# Sheet1.net
KiCad netlist of a schematic drawn in Altium Designer
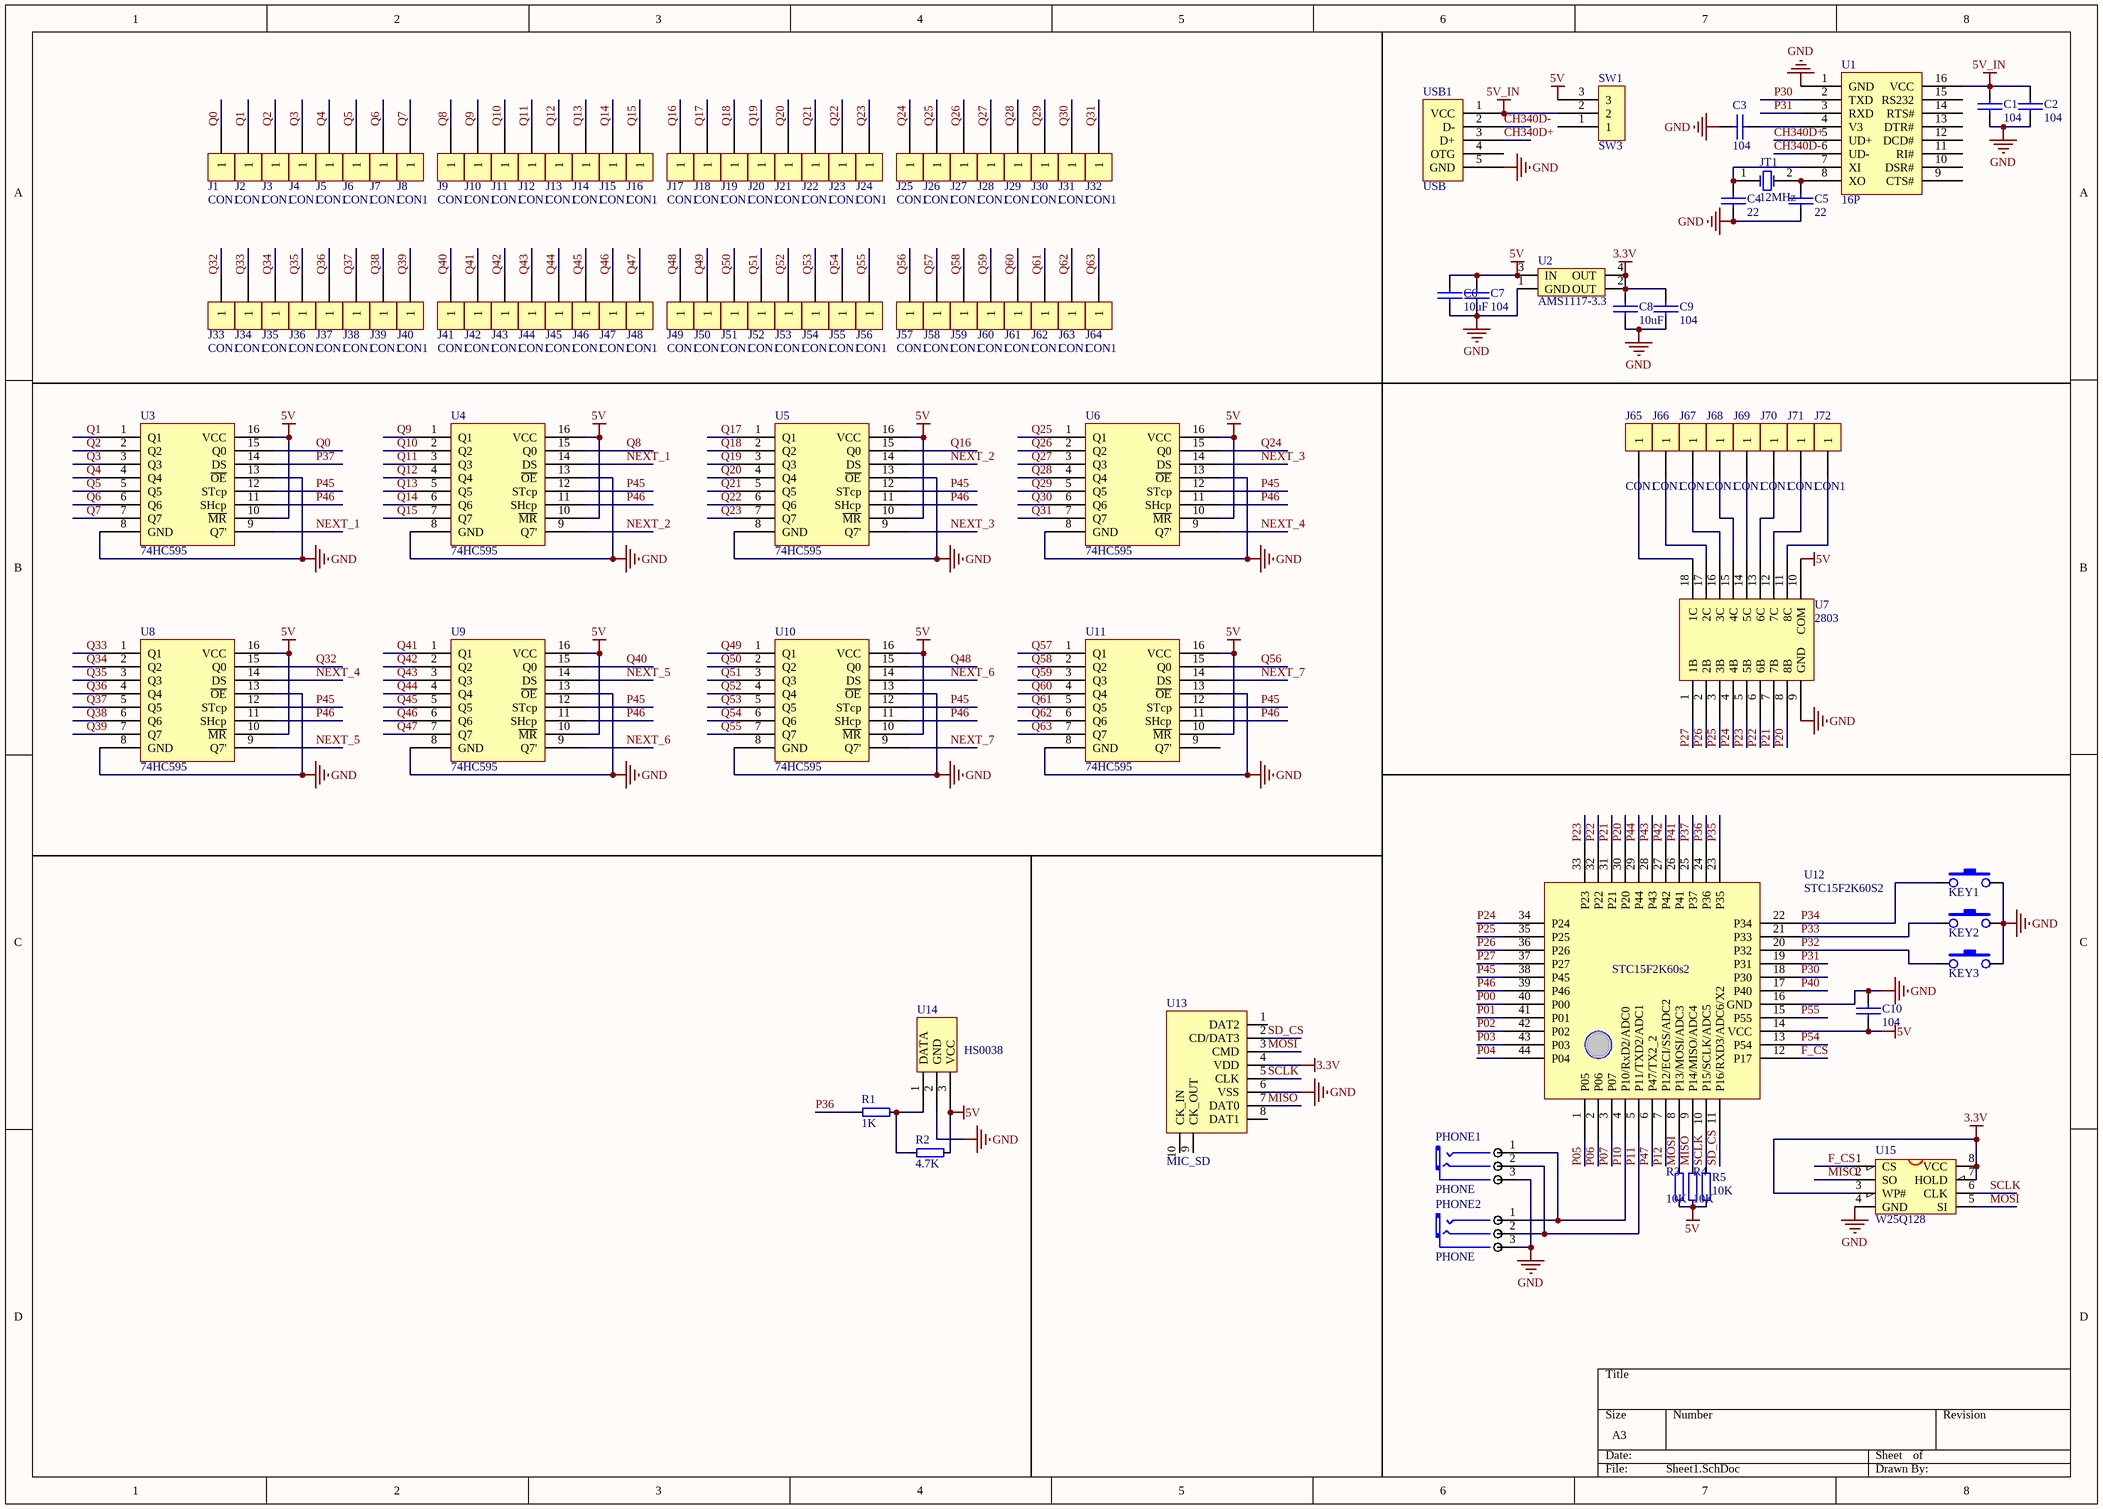
[diagram p0: Sheet1.SchDoc]

(export (version "E")
  (design (tool "Eeschema 10.0.6"))
  (components
    (comp (ref "C1") (value "104") (footprint "BY_魔法王子:0805C") (libsource (lib "BY_魔法王子") (part "CAP")))
    (comp (ref "C2") (value "104") (footprint "BY_魔法王子:0805C") (libsource (lib "BY_魔法王子") (part "CAP")))
    (comp (ref "C3") (value "104") (footprint "BY_魔法王子:0805C") (libsource (lib "BY_魔法王子") (part "CAP")))
    (comp (ref "C4") (value "22") (footprint "BY_魔法王子:0805C") (libsource (lib "BY_魔法王子") (part "CAP")))
    (comp (ref "C5") (value "22") (footprint "BY_魔法王子:0805C") (libsource (lib "BY_魔法王子") (part "CAP")))
    (comp (ref "C6") (value "10uF") (footprint "BY_魔法王子:0805C") (libsource (lib "BY_魔法王子") (part "CAP")))
    (comp (ref "C7") (value "104") (footprint "BY_魔法王子:0805C") (libsource (lib "BY_魔法王子") (part "CAP")))
    (comp (ref "C8") (value "10uF") (footprint "BY_魔法王子:0805C") (libsource (lib "BY_魔法王子") (part "CAP")))
    (comp (ref "C9") (value "104") (footprint "BY_魔法王子:0805C") (libsource (lib "BY_魔法王子") (part "CAP")))
    (comp (ref "C10") (value "104") (footprint "BY_魔法王子:0805C") (libsource (lib "BY_魔法王子") (part "CAP")))
    (comp (ref "J1")
      (value "CON1")
      (footprint "CON1")
      (description "Connector")
      (libsource (lib "插件") (part "CON1"))
    )
    (comp (ref "J2")
      (value "CON1")
      (footprint "CON1")
      (description "Connector")
      (libsource (lib "插件") (part "CON1"))
    )
    (comp (ref "J3")
      (value "CON1")
      (footprint "CON1")
      (description "Connector")
      (libsource (lib "插件") (part "CON1"))
    )
    (comp (ref "J4")
      (value "CON1")
      (footprint "CON1")
      (description "Connector")
      (libsource (lib "插件") (part "CON1"))
    )
    (comp (ref "J5")
      (value "CON1")
      (footprint "CON1")
      (description "Connector")
      (libsource (lib "插件") (part "CON1"))
    )
    (comp (ref "J6")
      (value "CON1")
      (footprint "CON1")
      (description "Connector")
      (libsource (lib "插件") (part "CON1"))
    )
    (comp (ref "J7")
      (value "CON1")
      (footprint "CON1")
      (description "Connector")
      (libsource (lib "插件") (part "CON1"))
    )
    (comp (ref "J8")
      (value "CON1")
      (footprint "CON1")
      (description "Connector")
      (libsource (lib "插件") (part "CON1"))
    )
    (comp (ref "J9")
      (value "CON1")
      (footprint "CON1")
      (description "Connector")
      (libsource (lib "插件") (part "CON1"))
    )
    (comp (ref "J10")
      (value "CON1")
      (footprint "CON1")
      (description "Connector")
      (libsource (lib "插件") (part "CON1"))
    )
    (comp (ref "J11")
      (value "CON1")
      (footprint "CON1")
      (description "Connector")
      (libsource (lib "插件") (part "CON1"))
    )
    (comp (ref "J12")
      (value "CON1")
      (footprint "CON1")
      (description "Connector")
      (libsource (lib "插件") (part "CON1"))
    )
    (comp (ref "J13")
      (value "CON1")
      (footprint "CON1")
      (description "Connector")
      (libsource (lib "插件") (part "CON1"))
    )
    (comp (ref "J14")
      (value "CON1")
      (footprint "CON1")
      (description "Connector")
      (libsource (lib "插件") (part "CON1"))
    )
    (comp (ref "J15")
      (value "CON1")
      (footprint "CON1")
      (description "Connector")
      (libsource (lib "插件") (part "CON1"))
    )
    (comp (ref "J16")
      (value "CON1")
      (footprint "CON1")
      (description "Connector")
      (libsource (lib "插件") (part "CON1"))
    )
    (comp (ref "J17")
      (value "CON1")
      (footprint "CON1")
      (description "Connector")
      (libsource (lib "插件") (part "CON1"))
    )
    (comp (ref "J18")
      (value "CON1")
      (footprint "CON1")
      (description "Connector")
      (libsource (lib "插件") (part "CON1"))
    )
    (comp (ref "J19")
      (value "CON1")
      (footprint "CON1")
      (description "Connector")
      (libsource (lib "插件") (part "CON1"))
    )
    (comp (ref "J20")
      (value "CON1")
      (footprint "CON1")
      (description "Connector")
      (libsource (lib "插件") (part "CON1"))
    )
    (comp (ref "J21")
      (value "CON1")
      (footprint "CON1")
      (description "Connector")
      (libsource (lib "插件") (part "CON1"))
    )
    (comp (ref "J22")
      (value "CON1")
      (footprint "CON1")
      (description "Connector")
      (libsource (lib "插件") (part "CON1"))
    )
    (comp (ref "J23")
      (value "CON1")
      (footprint "CON1")
      (description "Connector")
      (libsource (lib "插件") (part "CON1"))
    )
    (comp (ref "J24")
      (value "CON1")
      (footprint "CON1")
      (description "Connector")
      (libsource (lib "插件") (part "CON1"))
    )
    (comp (ref "J25")
      (value "CON1")
      (footprint "CON1")
      (description "Connector")
      (libsource (lib "插件") (part "CON1"))
    )
    (comp (ref "J26")
      (value "CON1")
      (footprint "CON1")
      (description "Connector")
      (libsource (lib "插件") (part "CON1"))
    )
    (comp (ref "J27")
      (value "CON1")
      (footprint "CON1")
      (description "Connector")
      (libsource (lib "插件") (part "CON1"))
    )
    (comp (ref "J28")
      (value "CON1")
      (footprint "CON1")
      (description "Connector")
      (libsource (lib "插件") (part "CON1"))
    )
    (comp (ref "J29")
      (value "CON1")
      (footprint "CON1")
      (description "Connector")
      (libsource (lib "插件") (part "CON1"))
    )
    (comp (ref "J30")
      (value "CON1")
      (footprint "CON1")
      (description "Connector")
      (libsource (lib "插件") (part "CON1"))
    )
    (comp (ref "J31")
      (value "CON1")
      (footprint "CON1")
      (description "Connector")
      (libsource (lib "插件") (part "CON1"))
    )
    (comp (ref "J32")
      (value "CON1")
      (footprint "CON1")
      (description "Connector")
      (libsource (lib "插件") (part "CON1"))
    )
    (comp (ref "J33")
      (value "CON1")
      (footprint "CON1")
      (description "Connector")
      (libsource (lib "插件") (part "CON1"))
    )
    (comp (ref "J34")
      (value "CON1")
      (footprint "CON1")
      (description "Connector")
      (libsource (lib "插件") (part "CON1"))
    )
    (comp (ref "J35")
      (value "CON1")
      (footprint "CON1")
      (description "Connector")
      (libsource (lib "插件") (part "CON1"))
    )
    (comp (ref "J36")
      (value "CON1")
      (footprint "CON1")
      (description "Connector")
      (libsource (lib "插件") (part "CON1"))
    )
    (comp (ref "J37")
      (value "CON1")
      (footprint "CON1")
      (description "Connector")
      (libsource (lib "插件") (part "CON1"))
    )
    (comp (ref "J38")
      (value "CON1")
      (footprint "CON1")
      (description "Connector")
      (libsource (lib "插件") (part "CON1"))
    )
    (comp (ref "J39")
      (value "CON1")
      (footprint "CON1")
      (description "Connector")
      (libsource (lib "插件") (part "CON1"))
    )
    (comp (ref "J40")
      (value "CON1")
      (footprint "CON1")
      (description "Connector")
      (libsource (lib "插件") (part "CON1"))
    )
    (comp (ref "J41")
      (value "CON1")
      (footprint "CON1")
      (description "Connector")
      (libsource (lib "插件") (part "CON1"))
    )
    (comp (ref "J42")
      (value "CON1")
      (footprint "CON1")
      (description "Connector")
      (libsource (lib "插件") (part "CON1"))
    )
    (comp (ref "J43")
      (value "CON1")
      (footprint "CON1")
      (description "Connector")
      (libsource (lib "插件") (part "CON1"))
    )
    (comp (ref "J44")
      (value "CON1")
      (footprint "CON1")
      (description "Connector")
      (libsource (lib "插件") (part "CON1"))
    )
    (comp (ref "J45")
      (value "CON1")
      (footprint "CON1")
      (description "Connector")
      (libsource (lib "插件") (part "CON1"))
    )
    (comp (ref "J46")
      (value "CON1")
      (footprint "CON1")
      (description "Connector")
      (libsource (lib "插件") (part "CON1"))
    )
    (comp (ref "J47")
      (value "CON1")
      (footprint "CON1")
      (description "Connector")
      (libsource (lib "插件") (part "CON1"))
    )
    (comp (ref "J48")
      (value "CON1")
      (footprint "CON1")
      (description "Connector")
      (libsource (lib "插件") (part "CON1"))
    )
    (comp (ref "J49")
      (value "CON1")
      (footprint "CON1")
      (description "Connector")
      (libsource (lib "插件") (part "CON1"))
    )
    (comp (ref "J50")
      (value "CON1")
      (footprint "CON1")
      (description "Connector")
      (libsource (lib "插件") (part "CON1"))
    )
    (comp (ref "J51")
      (value "CON1")
      (footprint "CON1")
      (description "Connector")
      (libsource (lib "插件") (part "CON1"))
    )
    (comp (ref "J52")
      (value "CON1")
      (footprint "CON1")
      (description "Connector")
      (libsource (lib "插件") (part "CON1"))
    )
    (comp (ref "J53")
      (value "CON1")
      (footprint "CON1")
      (description "Connector")
      (libsource (lib "插件") (part "CON1"))
    )
    (comp (ref "J54")
      (value "CON1")
      (footprint "CON1")
      (description "Connector")
      (libsource (lib "插件") (part "CON1"))
    )
    (comp (ref "J55")
      (value "CON1")
      (footprint "CON1")
      (description "Connector")
      (libsource (lib "插件") (part "CON1"))
    )
    (comp (ref "J56")
      (value "CON1")
      (footprint "CON1")
      (description "Connector")
      (libsource (lib "插件") (part "CON1"))
    )
    (comp (ref "J57")
      (value "CON1")
      (footprint "CON1")
      (description "Connector")
      (libsource (lib "插件") (part "CON1"))
    )
    (comp (ref "J58")
      (value "CON1")
      (footprint "CON1")
      (description "Connector")
      (libsource (lib "插件") (part "CON1"))
    )
    (comp (ref "J59")
      (value "CON1")
      (footprint "CON1")
      (description "Connector")
      (libsource (lib "插件") (part "CON1"))
    )
    (comp (ref "J60")
      (value "CON1")
      (footprint "CON1")
      (description "Connector")
      (libsource (lib "插件") (part "CON1"))
    )
    (comp (ref "J61")
      (value "CON1")
      (footprint "CON1")
      (description "Connector")
      (libsource (lib "插件") (part "CON1"))
    )
    (comp (ref "J62")
      (value "CON1")
      (footprint "CON1")
      (description "Connector")
      (libsource (lib "插件") (part "CON1"))
    )
    (comp (ref "J63")
      (value "CON1")
      (footprint "CON1")
      (description "Connector")
      (libsource (lib "插件") (part "CON1"))
    )
    (comp (ref "J64")
      (value "CON1")
      (footprint "CON1")
      (description "Connector")
      (libsource (lib "插件") (part "CON1"))
    )
    (comp (ref "J65")
      (value "CON1")
      (footprint "CON1")
      (description "Connector")
      (libsource (lib "") (part "CON1_1"))
    )
    (comp (ref "J66")
      (value "CON1")
      (footprint "CON1")
      (description "Connector")
      (libsource (lib "") (part "CON1_1"))
    )
    (comp (ref "J67")
      (value "CON1")
      (footprint "CON1")
      (description "Connector")
      (libsource (lib "") (part "CON1_1"))
    )
    (comp (ref "J68")
      (value "CON1")
      (footprint "CON1")
      (description "Connector")
      (libsource (lib "") (part "CON1_1"))
    )
    (comp (ref "J69")
      (value "CON1")
      (footprint "CON1")
      (description "Connector")
      (libsource (lib "") (part "CON1_1"))
    )
    (comp (ref "J70")
      (value "CON1")
      (footprint "CON1")
      (description "Connector")
      (libsource (lib "") (part "CON1_1"))
    )
    (comp (ref "J71")
      (value "CON1")
      (footprint "CON1")
      (description "Connector")
      (libsource (lib "") (part "CON1_1"))
    )
    (comp (ref "J72")
      (value "CON1")
      (footprint "CON1")
      (description "Connector")
      (libsource (lib "") (part "CON1_1"))
    )
    (comp (ref "JT1")
      (value "12MHz")
      (footprint "BY_魔法王子:JZ")
      (description "Crystal Oscillator")
      (fields (field (name "PUBLISHER") "Altium Limited"))
      (libsource (lib "Explorer STM32F407封装库") (part "XTAL"))
    )
    (comp (ref "KEY1") (value "KEY") (footprint "BY_魔法王子:KEY2") (libsource (lib "BY_魔法王子") (part "KEY")))
    (comp (ref "KEY2") (value "KEY") (footprint "BY_魔法王子:KEY2") (libsource (lib "BY_魔法王子") (part "KEY")))
    (comp (ref "KEY3") (value "KEY") (footprint "BY_魔法王子:KEY2") (libsource (lib "BY_魔法王子") (part "KEY")))
    (comp (ref "PHONE1")
      (value "PHONE")
      (footprint "PHONE_ST")
      (libsource (lib "Explorer STM32F407封装库") (part "PHONE_M"))
    )
    (comp (ref "PHONE2")
      (value "PHONE")
      (footprint "PHONE_ST")
      (libsource (lib "Explorer STM32F407封装库") (part "PHONE_M"))
    )
    (comp (ref "R1") (value "1K") (footprint "BY_魔法王子:0805R") (libsource (lib "BY_魔法王子") (part "RES")))
    (comp (ref "R2") (value "4.7K") (footprint "BY_魔法王子:0805R") (libsource (lib "BY_魔法王子") (part "RES")))
    (comp (ref "R3") (value "10K") (footprint "BY_魔法王子:0805R") (libsource (lib "BY_魔法王子") (part "RES")))
    (comp (ref "R4") (value "10K") (footprint "BY_魔法王子:0805R") (libsource (lib "BY_魔法王子") (part "RES")))
    (comp (ref "R5") (value "10K") (footprint "BY_魔法王子:0805R") (libsource (lib "BY_魔法王子") (part "RES")))
    (comp (ref "SW1") (value "SW3") (footprint "BY_魔法王子:SW3") (libsource (lib "BY_魔法王子") (part "SW3")))
    (comp (ref "U1") (value "16P") (footprint "CH340G") (libsource (lib "CH340G") (part "CH340G")))
    (comp (ref "U2")
      (value "AMS1117-3.3")
      (footprint "AMS1117")
      (libsource (lib "Explorer STM32F407封装库") (part "AMS1117"))
    )
    (comp (ref "U3") (value "74HC595") (footprint "SO-16N") (libsource (lib "74HC595") (part "74HC595")))
    (comp (ref "U4") (value "74HC595") (footprint "SO-16N") (libsource (lib "74HC595") (part "74HC595")))
    (comp (ref "U5") (value "74HC595") (footprint "SO-16N") (libsource (lib "74HC595") (part "74HC595")))
    (comp (ref "U6") (value "74HC595") (footprint "SO-16N") (libsource (lib "74HC595") (part "74HC595")))
    (comp (ref "U7") (value "2803") (footprint "BY_魔法王子:SOP-18") (libsource (lib "MISCESCH") (part "2803")))
    (comp (ref "U8") (value "74HC595") (footprint "SO-16N") (libsource (lib "74HC595") (part "74HC595")))
    (comp (ref "U9") (value "74HC595") (footprint "SO-16N") (libsource (lib "74HC595") (part "74HC595")))
    (comp (ref "U10") (value "74HC595") (footprint "SO-16N") (libsource (lib "74HC595") (part "74HC595")))
    (comp (ref "U11") (value "74HC595") (footprint "SO-16N") (libsource (lib "74HC595") (part "74HC595")))
    (comp (ref "U12")
      (value "STC15F2K60S2")
      (footprint "BY_魔法王子:STC15F2K60S2")
      (libsource (lib "BY_魔法王子") (part "STC15F2K60S2"))
    )
    (comp (ref "U13")
      (value "MIC_SD")
      (footprint "BY_魔法王子:TF_CARD")
      (libsource (lib "BY_魔法王子") (part "MICSD"))
    )
    (comp (ref "U14")
      (value "HS0038")
      (footprint "HS0038")
      (libsource (lib "Explorer STM32F407封装库") (part "HS0038"))
    )
    (comp (ref "U15")
      (value "W25Q128")
      (footprint "SOIC-8")
      (description "W25X16;SST25VF016;MX25L1605")
      (libsource (lib "Explorer STM32F407封装库") (part "W25X16"))
    )
    (comp (ref "USB1") (value "USB") (footprint "MINIUSB") (libsource (lib "MIN_USB") (part "MINIUSB")))
  )
  (nets
    (net (code "1") (name "/CH340D+") (class "Default")
      (node (ref "U1") (pin "5") (pinfunction "UD+_5") (pintype "passive"))
      (node (ref "USB1") (pin "3") (pinfunction "D+_3") (pintype "passive"))
    )
    (net (code "2") (name "/CH340D-") (class "Default")
      (node (ref "U1") (pin "6") (pinfunction "UD-_6") (pintype "passive"))
      (node (ref "USB1") (pin "2") (pinfunction "D-_2") (pintype "passive"))
    )
    (net (code "3") (name "/F_CS") (class "Default")
      (node (ref "U12") (pin "12") (pinfunction "P17_12") (pintype "passive"))
      (node (ref "U15") (pin "1") (pinfunction "CS_1") (pintype "passive"))
    )
    (net (code "4") (name "/MISO") (class "Default")
      (node (ref "R4") (pin "2") (pinfunction "2_2") (pintype "passive"))
      (node (ref "U12") (pin "9") (pinfunction "P14/MISO/ADC4_9") (pintype "passive"))
      (node (ref "U13") (pin "7") (pinfunction "DAT0_7") (pintype "passive"))
      (node (ref "U15") (pin "2") (pinfunction "SO_2") (pintype "passive"))
    )
    (net (code "5") (name "/MOSI") (class "Default")
      (node (ref "R3") (pin "2") (pinfunction "2_2") (pintype "passive"))
      (node (ref "U12") (pin "8") (pinfunction "P13/MOSI/ADC3_8") (pintype "passive"))
      (node (ref "U13") (pin "3") (pinfunction "CMD_3") (pintype "passive"))
      (node (ref "U15") (pin "5") (pinfunction "SI_5") (pintype "passive"))
    )
    (net (code "6") (name "/NEXT_1") (class "Default")
      (node (ref "U3") (pin "9") (pinfunction "Q7'_9") (pintype "passive"))
      (node (ref "U4") (pin "14") (pinfunction "DS_14") (pintype "passive"))
    )
    (net (code "7") (name "/NEXT_2") (class "Default")
      (node (ref "U4") (pin "9") (pinfunction "Q7'_9") (pintype "passive"))
      (node (ref "U5") (pin "14") (pinfunction "DS_14") (pintype "passive"))
    )
    (net (code "8") (name "/NEXT_3") (class "Default")
      (node (ref "U5") (pin "9") (pinfunction "Q7'_9") (pintype "passive"))
      (node (ref "U6") (pin "14") (pinfunction "DS_14") (pintype "passive"))
    )
    (net (code "9") (name "/NEXT_4") (class "Default")
      (node (ref "U6") (pin "9") (pinfunction "Q7'_9") (pintype "passive"))
      (node (ref "U8") (pin "14") (pinfunction "DS_14") (pintype "passive"))
    )
    (net (code "10") (name "/NEXT_5") (class "Default")
      (node (ref "U8") (pin "9") (pinfunction "Q7'_9") (pintype "passive"))
      (node (ref "U9") (pin "14") (pinfunction "DS_14") (pintype "passive"))
    )
    (net (code "11") (name "/NEXT_6") (class "Default")
      (node (ref "U10") (pin "14") (pinfunction "DS_14") (pintype "passive"))
      (node (ref "U9") (pin "9") (pinfunction "Q7'_9") (pintype "passive"))
    )
    (net (code "12") (name "/NEXT_7") (class "Default")
      (node (ref "U10") (pin "9") (pinfunction "Q7'_9") (pintype "passive"))
      (node (ref "U11") (pin "14") (pinfunction "DS_14") (pintype "passive"))
    )
    (net (code "13") (name "/P00") (class "Default")
      (node (ref "U12") (pin "40") (pinfunction "P00_40") (pintype "passive"))
    )
    (net (code "14") (name "/P01") (class "Default")
      (node (ref "U12") (pin "41") (pinfunction "P01_41") (pintype "passive"))
    )
    (net (code "15") (name "/P02") (class "Default")
      (node (ref "U12") (pin "42") (pinfunction "P02_42") (pintype "passive"))
    )
    (net (code "16") (name "/P03") (class "Default")
      (node (ref "U12") (pin "43") (pinfunction "P03_43") (pintype "passive"))
    )
    (net (code "17") (name "/P04") (class "Default")
      (node (ref "U12") (pin "44") (pinfunction "P04_44") (pintype "passive"))
    )
    (net (code "18") (name "/P05") (class "Default")
      (node (ref "U12") (pin "1") (pinfunction "P05_1") (pintype "passive"))
    )
    (net (code "19") (name "/P06") (class "Default")
      (node (ref "U12") (pin "2") (pinfunction "P06_2") (pintype "passive"))
    )
    (net (code "20") (name "/P07") (class "Default")
      (node (ref "U12") (pin "3") (pinfunction "P07_3") (pintype "passive"))
    )
    (net (code "21") (name "/P10") (class "Default")
      (node (ref "PHONE1") (pin "1") (pinfunction "CHL_1") (pintype "passive"))
      (node (ref "PHONE2") (pin "1") (pinfunction "CHL_1") (pintype "passive"))
      (node (ref "U12") (pin "4") (pinfunction "P10/RxD2/ADC0_4") (pintype "passive"))
    )
    (net (code "22") (name "/P11") (class "Default")
      (node (ref "PHONE1") (pin "2") (pinfunction "CHR_2") (pintype "passive"))
      (node (ref "PHONE2") (pin "2") (pinfunction "CHR_2") (pintype "passive"))
      (node (ref "U12") (pin "5") (pinfunction "P11/TXD2/ADC1_5") (pintype "passive"))
    )
    (net (code "23") (name "/P12") (class "Default")
      (node (ref "U12") (pin "7") (pinfunction "P12/ECI/SS/ADC2_7") (pintype "passive"))
    )
    (net (code "24") (name "/P20") (class "Default")
      (node (ref "U12") (pin "30") (pinfunction "P20_30") (pintype "passive"))
      (node (ref "U7") (pin "8") (pinfunction "8B_8") (pintype "passive"))
    )
    (net (code "25") (name "/P21") (class "Default")
      (node (ref "U12") (pin "31") (pinfunction "P21_31") (pintype "passive"))
      (node (ref "U7") (pin "7") (pinfunction "7B_7") (pintype "passive"))
    )
    (net (code "26") (name "/P22") (class "Default")
      (node (ref "U12") (pin "32") (pinfunction "P22_32") (pintype "passive"))
      (node (ref "U7") (pin "6") (pinfunction "6B_6") (pintype "passive"))
    )
    (net (code "27") (name "/P23") (class "Default")
      (node (ref "U12") (pin "33") (pinfunction "P23_33") (pintype "passive"))
      (node (ref "U7") (pin "5") (pinfunction "5B_5") (pintype "passive"))
    )
    (net (code "28") (name "/P24") (class "Default")
      (node (ref "U12") (pin "34") (pinfunction "P24_34") (pintype "passive"))
      (node (ref "U7") (pin "4") (pinfunction "4B_4") (pintype "passive"))
    )
    (net (code "29") (name "/P25") (class "Default")
      (node (ref "U12") (pin "35") (pinfunction "P25_35") (pintype "passive"))
      (node (ref "U7") (pin "3") (pinfunction "3B_3") (pintype "passive"))
    )
    (net (code "30") (name "/P26") (class "Default")
      (node (ref "U12") (pin "36") (pinfunction "P26_36") (pintype "passive"))
      (node (ref "U7") (pin "2") (pinfunction "2B_2") (pintype "passive"))
    )
    (net (code "31") (name "/P27") (class "Default")
      (node (ref "U12") (pin "37") (pinfunction "P27_37") (pintype "passive"))
      (node (ref "U7") (pin "1") (pinfunction "1B_1") (pintype "passive"))
    )
    (net (code "32") (name "/P30") (class "Default")
      (node (ref "U1") (pin "2") (pinfunction "TXD_2") (pintype "passive"))
      (node (ref "U12") (pin "18") (pinfunction "P30_18") (pintype "passive"))
    )
    (net (code "33") (name "/P31") (class "Default")
      (node (ref "U1") (pin "3") (pinfunction "RXD_3") (pintype "passive"))
      (node (ref "U12") (pin "19") (pinfunction "P31_19") (pintype "passive"))
    )
    (net (code "34") (name "/P32") (class "Default")
      (node (ref "KEY3") (pin "1") (pinfunction "1_1") (pintype "passive"))
      (node (ref "U12") (pin "20") (pinfunction "P32_20") (pintype "passive"))
    )
    (net (code "35") (name "/P33") (class "Default")
      (node (ref "KEY2") (pin "1") (pinfunction "1_1") (pintype "passive"))
      (node (ref "U12") (pin "21") (pinfunction "P33_21") (pintype "passive"))
    )
    (net (code "36") (name "/P34") (class "Default")
      (node (ref "KEY1") (pin "1") (pinfunction "1_1") (pintype "passive"))
      (node (ref "U12") (pin "22") (pinfunction "P34_22") (pintype "passive"))
    )
    (net (code "37") (name "/P35") (class "Default")
      (node (ref "U12") (pin "23") (pinfunction "P35_23") (pintype "passive"))
    )
    (net (code "38") (name "/P36") (class "Default")
      (node (ref "R1") (pin "2") (pinfunction "2_2") (pintype "passive"))
      (node (ref "U12") (pin "24") (pinfunction "P36_24") (pintype "passive"))
    )
    (net (code "39") (name "/P37") (class "Default")
      (node (ref "U12") (pin "25") (pinfunction "P37_25") (pintype "passive"))
      (node (ref "U3") (pin "14") (pinfunction "DS_14") (pintype "passive"))
    )
    (net (code "40") (name "/P40") (class "Default")
      (node (ref "U12") (pin "17") (pinfunction "P40_17") (pintype "passive"))
    )
    (net (code "41") (name "/P41") (class "Default")
      (node (ref "U12") (pin "26") (pinfunction "P41_26") (pintype "passive"))
    )
    (net (code "42") (name "/P42") (class "Default")
      (node (ref "U12") (pin "27") (pinfunction "P42_27") (pintype "passive"))
    )
    (net (code "43") (name "/P43") (class "Default")
      (node (ref "U12") (pin "28") (pinfunction "P43_28") (pintype "passive"))
    )
    (net (code "44") (name "/P44") (class "Default")
      (node (ref "U12") (pin "29") (pinfunction "P44_29") (pintype "passive"))
    )
    (net (code "45") (name "/P45") (class "Default")
      (node (ref "U10") (pin "12") (pinfunction "STcp_12") (pintype "passive"))
      (node (ref "U11") (pin "12") (pinfunction "STcp_12") (pintype "passive"))
      (node (ref "U12") (pin "38") (pinfunction "P45_38") (pintype "passive"))
      (node (ref "U3") (pin "12") (pinfunction "STcp_12") (pintype "passive"))
      (node (ref "U4") (pin "12") (pinfunction "STcp_12") (pintype "passive"))
      (node (ref "U5") (pin "12") (pinfunction "STcp_12") (pintype "passive"))
      (node (ref "U6") (pin "12") (pinfunction "STcp_12") (pintype "passive"))
      (node (ref "U8") (pin "12") (pinfunction "STcp_12") (pintype "passive"))
      (node (ref "U9") (pin "12") (pinfunction "STcp_12") (pintype "passive"))
    )
    (net (code "46") (name "/P46") (class "Default")
      (node (ref "U10") (pin "11") (pinfunction "SHcp_11") (pintype "passive"))
      (node (ref "U11") (pin "11") (pinfunction "SHcp_11") (pintype "passive"))
      (node (ref "U12") (pin "39") (pinfunction "P46_39") (pintype "passive"))
      (node (ref "U3") (pin "11") (pinfunction "SHcp_11") (pintype "passive"))
      (node (ref "U4") (pin "11") (pinfunction "SHcp_11") (pintype "passive"))
      (node (ref "U5") (pin "11") (pinfunction "SHcp_11") (pintype "passive"))
      (node (ref "U6") (pin "11") (pinfunction "SHcp_11") (pintype "passive"))
      (node (ref "U8") (pin "11") (pinfunction "SHcp_11") (pintype "passive"))
      (node (ref "U9") (pin "11") (pinfunction "SHcp_11") (pintype "passive"))
    )
    (net (code "47") (name "/P47") (class "Default")
      (node (ref "U12") (pin "6") (pinfunction "P47/TX2_2_6") (pintype "passive"))
    )
    (net (code "48") (name "/P54") (class "Default")
      (node (ref "U12") (pin "13") (pinfunction "P54_13") (pintype "passive"))
    )
    (net (code "49") (name "/P55") (class "Default")
      (node (ref "U12") (pin "15") (pinfunction "P55_15") (pintype "passive"))
    )
    (net (code "50") (name "/Q0") (class "Default")
      (node (ref "J1") (pin "1") (pinfunction "1_1") (pintype "passive"))
      (node (ref "U3") (pin "15") (pinfunction "Q0_15") (pintype "passive"))
    )
    (net (code "51") (name "/Q1") (class "Default")
      (node (ref "J2") (pin "1") (pinfunction "1_1") (pintype "passive"))
      (node (ref "U3") (pin "1") (pinfunction "Q1_1") (pintype "passive"))
    )
    (net (code "52") (name "/Q2") (class "Default")
      (node (ref "J3") (pin "1") (pinfunction "1_1") (pintype "passive"))
      (node (ref "U3") (pin "2") (pinfunction "Q2_2") (pintype "passive"))
    )
    (net (code "53") (name "/Q3") (class "Default")
      (node (ref "J4") (pin "1") (pinfunction "1_1") (pintype "passive"))
      (node (ref "U3") (pin "3") (pinfunction "Q3_3") (pintype "passive"))
    )
    (net (code "54") (name "/Q4") (class "Default")
      (node (ref "J5") (pin "1") (pinfunction "1_1") (pintype "passive"))
      (node (ref "U3") (pin "4") (pinfunction "Q4_4") (pintype "passive"))
    )
    (net (code "55") (name "/Q5") (class "Default")
      (node (ref "J6") (pin "1") (pinfunction "1_1") (pintype "passive"))
      (node (ref "U3") (pin "5") (pinfunction "Q5_5") (pintype "passive"))
    )
    (net (code "56") (name "/Q6") (class "Default")
      (node (ref "J7") (pin "1") (pinfunction "1_1") (pintype "passive"))
      (node (ref "U3") (pin "6") (pinfunction "Q6_6") (pintype "passive"))
    )
    (net (code "57") (name "/Q7") (class "Default")
      (node (ref "J8") (pin "1") (pinfunction "1_1") (pintype "passive"))
      (node (ref "U3") (pin "7") (pinfunction "Q7_7") (pintype "passive"))
    )
    (net (code "58") (name "/Q8") (class "Default")
      (node (ref "J9") (pin "1") (pinfunction "1_1") (pintype "passive"))
      (node (ref "U4") (pin "15") (pinfunction "Q0_15") (pintype "passive"))
    )
    (net (code "59") (name "/Q9") (class "Default")
      (node (ref "J10") (pin "1") (pinfunction "1_1") (pintype "passive"))
      (node (ref "U4") (pin "1") (pinfunction "Q1_1") (pintype "passive"))
    )
    (net (code "60") (name "/Q10") (class "Default")
      (node (ref "J11") (pin "1") (pinfunction "1_1") (pintype "passive"))
      (node (ref "U4") (pin "2") (pinfunction "Q2_2") (pintype "passive"))
    )
    (net (code "61") (name "/Q11") (class "Default")
      (node (ref "J12") (pin "1") (pinfunction "1_1") (pintype "passive"))
      (node (ref "U4") (pin "3") (pinfunction "Q3_3") (pintype "passive"))
    )
    (net (code "62") (name "/Q12") (class "Default")
      (node (ref "J13") (pin "1") (pinfunction "1_1") (pintype "passive"))
      (node (ref "U4") (pin "4") (pinfunction "Q4_4") (pintype "passive"))
    )
    (net (code "63") (name "/Q13") (class "Default")
      (node (ref "J14") (pin "1") (pinfunction "1_1") (pintype "passive"))
      (node (ref "U4") (pin "5") (pinfunction "Q5_5") (pintype "passive"))
    )
    (net (code "64") (name "/Q14") (class "Default")
      (node (ref "J15") (pin "1") (pinfunction "1_1") (pintype "passive"))
      (node (ref "U4") (pin "6") (pinfunction "Q6_6") (pintype "passive"))
    )
    (net (code "65") (name "/Q15") (class "Default")
      (node (ref "J16") (pin "1") (pinfunction "1_1") (pintype "passive"))
      (node (ref "U4") (pin "7") (pinfunction "Q7_7") (pintype "passive"))
    )
    (net (code "66") (name "/Q16") (class "Default")
      (node (ref "J17") (pin "1") (pinfunction "1_1") (pintype "passive"))
      (node (ref "U5") (pin "15") (pinfunction "Q0_15") (pintype "passive"))
    )
    (net (code "67") (name "/Q17") (class "Default")
      (node (ref "J18") (pin "1") (pinfunction "1_1") (pintype "passive"))
      (node (ref "U5") (pin "1") (pinfunction "Q1_1") (pintype "passive"))
    )
    (net (code "68") (name "/Q18") (class "Default")
      (node (ref "J19") (pin "1") (pinfunction "1_1") (pintype "passive"))
      (node (ref "U5") (pin "2") (pinfunction "Q2_2") (pintype "passive"))
    )
    (net (code "69") (name "/Q19") (class "Default")
      (node (ref "J20") (pin "1") (pinfunction "1_1") (pintype "passive"))
      (node (ref "U5") (pin "3") (pinfunction "Q3_3") (pintype "passive"))
    )
    (net (code "70") (name "/Q20") (class "Default")
      (node (ref "J21") (pin "1") (pinfunction "1_1") (pintype "passive"))
      (node (ref "U5") (pin "4") (pinfunction "Q4_4") (pintype "passive"))
    )
    (net (code "71") (name "/Q21") (class "Default")
      (node (ref "J22") (pin "1") (pinfunction "1_1") (pintype "passive"))
      (node (ref "U5") (pin "5") (pinfunction "Q5_5") (pintype "passive"))
    )
    (net (code "72") (name "/Q22") (class "Default")
      (node (ref "J23") (pin "1") (pinfunction "1_1") (pintype "passive"))
      (node (ref "U5") (pin "6") (pinfunction "Q6_6") (pintype "passive"))
    )
    (net (code "73") (name "/Q23") (class "Default")
      (node (ref "J24") (pin "1") (pinfunction "1_1") (pintype "passive"))
      (node (ref "U5") (pin "7") (pinfunction "Q7_7") (pintype "passive"))
    )
    (net (code "74") (name "/Q24") (class "Default")
      (node (ref "J25") (pin "1") (pinfunction "1_1") (pintype "passive"))
      (node (ref "U6") (pin "15") (pinfunction "Q0_15") (pintype "passive"))
    )
    (net (code "75") (name "/Q25") (class "Default")
      (node (ref "J26") (pin "1") (pinfunction "1_1") (pintype "passive"))
      (node (ref "U6") (pin "1") (pinfunction "Q1_1") (pintype "passive"))
    )
    (net (code "76") (name "/Q26") (class "Default")
      (node (ref "J27") (pin "1") (pinfunction "1_1") (pintype "passive"))
      (node (ref "U6") (pin "2") (pinfunction "Q2_2") (pintype "passive"))
    )
    (net (code "77") (name "/Q27") (class "Default")
      (node (ref "J28") (pin "1") (pinfunction "1_1") (pintype "passive"))
      (node (ref "U6") (pin "3") (pinfunction "Q3_3") (pintype "passive"))
    )
    (net (code "78") (name "/Q28") (class "Default")
      (node (ref "J29") (pin "1") (pinfunction "1_1") (pintype "passive"))
      (node (ref "U6") (pin "4") (pinfunction "Q4_4") (pintype "passive"))
    )
    (net (code "79") (name "/Q29") (class "Default")
      (node (ref "J30") (pin "1") (pinfunction "1_1") (pintype "passive"))
      (node (ref "U6") (pin "5") (pinfunction "Q5_5") (pintype "passive"))
    )
    (net (code "80") (name "/Q30") (class "Default")
      (node (ref "J31") (pin "1") (pinfunction "1_1") (pintype "passive"))
      (node (ref "U6") (pin "6") (pinfunction "Q6_6") (pintype "passive"))
    )
    (net (code "81") (name "/Q31") (class "Default")
      (node (ref "J32") (pin "1") (pinfunction "1_1") (pintype "passive"))
      (node (ref "U6") (pin "7") (pinfunction "Q7_7") (pintype "passive"))
    )
    (net (code "82") (name "/Q32") (class "Default")
      (node (ref "J33") (pin "1") (pinfunction "1_1") (pintype "passive"))
      (node (ref "U8") (pin "15") (pinfunction "Q0_15") (pintype "passive"))
    )
    (net (code "83") (name "/Q33") (class "Default")
      (node (ref "J34") (pin "1") (pinfunction "1_1") (pintype "passive"))
      (node (ref "U8") (pin "1") (pinfunction "Q1_1") (pintype "passive"))
    )
    (net (code "84") (name "/Q34") (class "Default")
      (node (ref "J35") (pin "1") (pinfunction "1_1") (pintype "passive"))
      (node (ref "U8") (pin "2") (pinfunction "Q2_2") (pintype "passive"))
    )
    (net (code "85") (name "/Q35") (class "Default")
      (node (ref "J36") (pin "1") (pinfunction "1_1") (pintype "passive"))
      (node (ref "U8") (pin "3") (pinfunction "Q3_3") (pintype "passive"))
    )
    (net (code "86") (name "/Q36") (class "Default")
      (node (ref "J37") (pin "1") (pinfunction "1_1") (pintype "passive"))
      (node (ref "U8") (pin "4") (pinfunction "Q4_4") (pintype "passive"))
    )
    (net (code "87") (name "/Q37") (class "Default")
      (node (ref "J38") (pin "1") (pinfunction "1_1") (pintype "passive"))
      (node (ref "U8") (pin "5") (pinfunction "Q5_5") (pintype "passive"))
    )
    (net (code "88") (name "/Q38") (class "Default")
      (node (ref "J39") (pin "1") (pinfunction "1_1") (pintype "passive"))
      (node (ref "U8") (pin "6") (pinfunction "Q6_6") (pintype "passive"))
    )
    (net (code "89") (name "/Q39") (class "Default")
      (node (ref "J40") (pin "1") (pinfunction "1_1") (pintype "passive"))
      (node (ref "U8") (pin "7") (pinfunction "Q7_7") (pintype "passive"))
    )
    (net (code "90") (name "/Q40") (class "Default")
      (node (ref "J41") (pin "1") (pinfunction "1_1") (pintype "passive"))
      (node (ref "U9") (pin "15") (pinfunction "Q0_15") (pintype "passive"))
    )
    (net (code "91") (name "/Q41") (class "Default")
      (node (ref "J42") (pin "1") (pinfunction "1_1") (pintype "passive"))
      (node (ref "U9") (pin "1") (pinfunction "Q1_1") (pintype "passive"))
    )
    (net (code "92") (name "/Q42") (class "Default")
      (node (ref "J43") (pin "1") (pinfunction "1_1") (pintype "passive"))
      (node (ref "U9") (pin "2") (pinfunction "Q2_2") (pintype "passive"))
    )
    (net (code "93") (name "/Q43") (class "Default")
      (node (ref "J44") (pin "1") (pinfunction "1_1") (pintype "passive"))
      (node (ref "U9") (pin "3") (pinfunction "Q3_3") (pintype "passive"))
    )
    (net (code "94") (name "/Q44") (class "Default")
      (node (ref "J45") (pin "1") (pinfunction "1_1") (pintype "passive"))
      (node (ref "U9") (pin "4") (pinfunction "Q4_4") (pintype "passive"))
    )
    (net (code "95") (name "/Q45") (class "Default")
      (node (ref "J46") (pin "1") (pinfunction "1_1") (pintype "passive"))
      (node (ref "U9") (pin "5") (pinfunction "Q5_5") (pintype "passive"))
    )
    (net (code "96") (name "/Q46") (class "Default")
      (node (ref "J47") (pin "1") (pinfunction "1_1") (pintype "passive"))
      (node (ref "U9") (pin "6") (pinfunction "Q6_6") (pintype "passive"))
    )
    (net (code "97") (name "/Q47") (class "Default")
      (node (ref "J48") (pin "1") (pinfunction "1_1") (pintype "passive"))
      (node (ref "U9") (pin "7") (pinfunction "Q7_7") (pintype "passive"))
    )
    (net (code "98") (name "/Q48") (class "Default")
      (node (ref "J49") (pin "1") (pinfunction "1_1") (pintype "passive"))
      (node (ref "U10") (pin "15") (pinfunction "Q0_15") (pintype "passive"))
    )
    (net (code "99") (name "/Q49") (class "Default")
      (node (ref "J50") (pin "1") (pinfunction "1_1") (pintype "passive"))
      (node (ref "U10") (pin "1") (pinfunction "Q1_1") (pintype "passive"))
    )
    (net (code "100") (name "/Q50") (class "Default")
      (node (ref "J51") (pin "1") (pinfunction "1_1") (pintype "passive"))
      (node (ref "U10") (pin "2") (pinfunction "Q2_2") (pintype "passive"))
    )
    (net (code "101") (name "/Q51") (class "Default")
      (node (ref "J52") (pin "1") (pinfunction "1_1") (pintype "passive"))
      (node (ref "U10") (pin "3") (pinfunction "Q3_3") (pintype "passive"))
    )
    (net (code "102") (name "/Q52") (class "Default")
      (node (ref "J53") (pin "1") (pinfunction "1_1") (pintype "passive"))
      (node (ref "U10") (pin "4") (pinfunction "Q4_4") (pintype "passive"))
    )
    (net (code "103") (name "/Q53") (class "Default")
      (node (ref "J54") (pin "1") (pinfunction "1_1") (pintype "passive"))
      (node (ref "U10") (pin "5") (pinfunction "Q5_5") (pintype "passive"))
    )
    (net (code "104") (name "/Q54") (class "Default")
      (node (ref "J55") (pin "1") (pinfunction "1_1") (pintype "passive"))
      (node (ref "U10") (pin "6") (pinfunction "Q6_6") (pintype "passive"))
    )
    (net (code "105") (name "/Q55") (class "Default")
      (node (ref "J56") (pin "1") (pinfunction "1_1") (pintype "passive"))
      (node (ref "U10") (pin "7") (pinfunction "Q7_7") (pintype "passive"))
    )
    (net (code "106") (name "/Q56") (class "Default")
      (node (ref "J57") (pin "1") (pinfunction "1_1") (pintype "passive"))
      (node (ref "U11") (pin "15") (pinfunction "Q0_15") (pintype "passive"))
    )
    (net (code "107") (name "/Q57") (class "Default")
      (node (ref "J58") (pin "1") (pinfunction "1_1") (pintype "passive"))
      (node (ref "U11") (pin "1") (pinfunction "Q1_1") (pintype "passive"))
    )
    (net (code "108") (name "/Q58") (class "Default")
      (node (ref "J59") (pin "1") (pinfunction "1_1") (pintype "passive"))
      (node (ref "U11") (pin "2") (pinfunction "Q2_2") (pintype "passive"))
    )
    (net (code "109") (name "/Q59") (class "Default")
      (node (ref "J60") (pin "1") (pinfunction "1_1") (pintype "passive"))
      (node (ref "U11") (pin "3") (pinfunction "Q3_3") (pintype "passive"))
    )
    (net (code "110") (name "/Q60") (class "Default")
      (node (ref "J61") (pin "1") (pinfunction "1_1") (pintype "passive"))
      (node (ref "U11") (pin "4") (pinfunction "Q4_4") (pintype "passive"))
    )
    (net (code "111") (name "/Q61") (class "Default")
      (node (ref "J62") (pin "1") (pinfunction "1_1") (pintype "passive"))
      (node (ref "U11") (pin "5") (pinfunction "Q5_5") (pintype "passive"))
    )
    (net (code "112") (name "/Q62") (class "Default")
      (node (ref "J63") (pin "1") (pinfunction "1_1") (pintype "passive"))
      (node (ref "U11") (pin "6") (pinfunction "Q6_6") (pintype "passive"))
    )
    (net (code "113") (name "/Q63") (class "Default")
      (node (ref "J64") (pin "1") (pinfunction "1_1") (pintype "passive"))
      (node (ref "U11") (pin "7") (pinfunction "Q7_7") (pintype "passive"))
    )
    (net (code "114") (name "/SCLK") (class "Default")
      (node (ref "R5") (pin "2") (pinfunction "2_2") (pintype "passive"))
      (node (ref "U12") (pin "10") (pinfunction "P15/SCLK/ADC5_10") (pintype "passive"))
      (node (ref "U13") (pin "5") (pinfunction "CLK_5") (pintype "passive"))
      (node (ref "U15") (pin "6") (pinfunction "CLK_6") (pintype "passive"))
    )
    (net (code "115") (name "/SD_CS") (class "Default")
      (node (ref "U12") (pin "11") (pinfunction "P16/RXD3/ADC6/X2_11") (pintype "passive"))
      (node (ref "U13") (pin "2") (pinfunction "CD/DAT3_2") (pintype "passive"))
    )
    (net (code "116") (name "3.3V") (class "Default")
      (node (ref "C8") (pin "1") (pinfunction "1_1") (pintype "passive"))
      (node (ref "C9") (pin "1") (pinfunction "1_1") (pintype "passive"))
      (node (ref "U13") (pin "4") (pinfunction "VDD_4") (pintype "passive"))
      (node (ref "U15") (pin "3") (pinfunction "WP#_3") (pintype "passive"))
      (node (ref "U15") (pin "7") (pinfunction "HOLD_7") (pintype "passive"))
      (node (ref "U15") (pin "8") (pinfunction "VCC_8") (pintype "passive"))
      (node (ref "U2") (pin "2") (pinfunction "OUT_2") (pintype "passive"))
      (node (ref "U2") (pin "4") (pinfunction "OUT_4") (pintype "passive"))
    )
    (net (code "117") (name "5V") (class "Default")
      (node (ref "C10") (pin "2") (pinfunction "2_2") (pintype "passive"))
      (node (ref "C6") (pin "1") (pinfunction "1_1") (pintype "passive"))
      (node (ref "C7") (pin "1") (pinfunction "1_1") (pintype "passive"))
      (node (ref "R2") (pin "1") (pinfunction "1_1") (pintype "passive"))
      (node (ref "R3") (pin "1") (pinfunction "1_1") (pintype "passive"))
      (node (ref "R4") (pin "1") (pinfunction "1_1") (pintype "passive"))
      (node (ref "R5") (pin "1") (pinfunction "1_1") (pintype "passive"))
      (node (ref "SW1") (pin "3") (pinfunction "3_3") (pintype "passive"))
      (node (ref "U10") (pin "10") (pinfunction "~{MR}_10") (pintype "passive"))
      (node (ref "U10") (pin "16") (pinfunction "VCC_16") (pintype "passive"))
      (node (ref "U11") (pin "10") (pinfunction "~{MR}_10") (pintype "passive"))
      (node (ref "U11") (pin "16") (pinfunction "VCC_16") (pintype "passive"))
      (node (ref "U12") (pin "14") (pinfunction "VCC_14") (pintype "passive"))
      (node (ref "U14") (pin "3") (pinfunction "VCC_3") (pintype "passive"))
      (node (ref "U2") (pin "3") (pinfunction "IN_3") (pintype "passive"))
      (node (ref "U3") (pin "10") (pinfunction "~{MR}_10") (pintype "passive"))
      (node (ref "U3") (pin "16") (pinfunction "VCC_16") (pintype "passive"))
      (node (ref "U4") (pin "10") (pinfunction "~{MR}_10") (pintype "passive"))
      (node (ref "U4") (pin "16") (pinfunction "VCC_16") (pintype "passive"))
      (node (ref "U5") (pin "10") (pinfunction "~{MR}_10") (pintype "passive"))
      (node (ref "U5") (pin "16") (pinfunction "VCC_16") (pintype "passive"))
      (node (ref "U6") (pin "10") (pinfunction "~{MR}_10") (pintype "passive"))
      (node (ref "U6") (pin "16") (pinfunction "VCC_16") (pintype "passive"))
      (node (ref "U7") (pin "10") (pinfunction "COM_10") (pintype "passive"))
      (node (ref "U8") (pin "10") (pinfunction "~{MR}_10") (pintype "passive"))
      (node (ref "U8") (pin "16") (pinfunction "VCC_16") (pintype "passive"))
      (node (ref "U9") (pin "10") (pinfunction "~{MR}_10") (pintype "passive"))
      (node (ref "U9") (pin "16") (pinfunction "VCC_16") (pintype "passive"))
    )
    (net (code "118") (name "5V_IN") (class "Default")
      (node (ref "C1") (pin "1") (pinfunction "1_1") (pintype "passive"))
      (node (ref "C2") (pin "1") (pinfunction "1_1") (pintype "passive"))
      (node (ref "SW1") (pin "2") (pinfunction "2_2") (pintype "passive"))
      (node (ref "U1") (pin "16") (pinfunction "VCC_16") (pintype "passive"))
      (node (ref "USB1") (pin "1") (pinfunction "VCC_1") (pintype "passive"))
    )
    (net (code "119") (name "GND") (class "Default")
      (node (ref "C1") (pin "2") (pinfunction "2_2") (pintype "passive"))
      (node (ref "C10") (pin "1") (pinfunction "1_1") (pintype "passive"))
      (node (ref "C2") (pin "2") (pinfunction "2_2") (pintype "passive"))
      (node (ref "C3") (pin "1") (pinfunction "1_1") (pintype "passive"))
      (node (ref "C4") (pin "2") (pinfunction "2_2") (pintype "passive"))
      (node (ref "C5") (pin "2") (pinfunction "2_2") (pintype "passive"))
      (node (ref "C6") (pin "2") (pinfunction "2_2") (pintype "passive"))
      (node (ref "C7") (pin "2") (pinfunction "2_2") (pintype "passive"))
      (node (ref "C8") (pin "2") (pinfunction "2_2") (pintype "passive"))
      (node (ref "C9") (pin "2") (pinfunction "2_2") (pintype "passive"))
      (node (ref "KEY1") (pin "2") (pinfunction "2_2") (pintype "passive"))
      (node (ref "KEY2") (pin "2") (pinfunction "2_2") (pintype "passive"))
      (node (ref "KEY3") (pin "2") (pinfunction "2_2") (pintype "passive"))
      (node (ref "PHONE1") (pin "3") (pinfunction "COM_3") (pintype "passive"))
      (node (ref "PHONE2") (pin "3") (pinfunction "COM_3") (pintype "passive"))
      (node (ref "U1") (pin "1") (pinfunction "GND_1") (pintype "passive"))
      (node (ref "U10") (pin "13") (pinfunction "~{OE}_13") (pintype "passive"))
      (node (ref "U10") (pin "8") (pinfunction "GND_8") (pintype "passive"))
      (node (ref "U11") (pin "13") (pinfunction "~{OE}_13") (pintype "passive"))
      (node (ref "U11") (pin "8") (pinfunction "GND_8") (pintype "passive"))
      (node (ref "U12") (pin "16") (pinfunction "GND_16") (pintype "passive"))
      (node (ref "U13") (pin "6") (pinfunction "VSS_6") (pintype "passive"))
      (node (ref "U14") (pin "2") (pinfunction "GND_2") (pintype "passive"))
      (node (ref "U15") (pin "4") (pinfunction "GND_4") (pintype "passive"))
      (node (ref "U2") (pin "1") (pinfunction "GND_1") (pintype "passive"))
      (node (ref "U3") (pin "13") (pinfunction "~{OE}_13") (pintype "passive"))
      (node (ref "U3") (pin "8") (pinfunction "GND_8") (pintype "passive"))
      (node (ref "U4") (pin "13") (pinfunction "~{OE}_13") (pintype "passive"))
      (node (ref "U4") (pin "8") (pinfunction "GND_8") (pintype "passive"))
      (node (ref "U5") (pin "13") (pinfunction "~{OE}_13") (pintype "passive"))
      (node (ref "U5") (pin "8") (pinfunction "GND_8") (pintype "passive"))
      (node (ref "U6") (pin "13") (pinfunction "~{OE}_13") (pintype "passive"))
      (node (ref "U6") (pin "8") (pinfunction "GND_8") (pintype "passive"))
      (node (ref "U7") (pin "9") (pinfunction "GND_9") (pintype "passive"))
      (node (ref "U8") (pin "13") (pinfunction "~{OE}_13") (pintype "passive"))
      (node (ref "U8") (pin "8") (pinfunction "GND_8") (pintype "passive"))
      (node (ref "U9") (pin "13") (pinfunction "~{OE}_13") (pintype "passive"))
      (node (ref "U9") (pin "8") (pinfunction "GND_8") (pintype "passive"))
      (node (ref "USB1") (pin "5") (pinfunction "GND_5") (pintype "passive"))
    )
    (net (code "120") (name "Net-(JT1-OSC1)") (class "Default")
      (node (ref "C4") (pin "1") (pinfunction "1_1") (pintype "passive"))
      (node (ref "JT1") (pin "1") (pinfunction "OSC1_1") (pintype "passive"))
      (node (ref "U1") (pin "7") (pinfunction "XI_7") (pintype "passive"))
    )
    (net (code "121") (name "Net-(JT1-OSC2)") (class "Default")
      (node (ref "C5") (pin "1") (pinfunction "1_1") (pintype "passive"))
      (node (ref "JT1") (pin "2") (pinfunction "OSC2_2") (pintype "passive"))
      (node (ref "U1") (pin "8") (pinfunction "XO_8") (pintype "passive"))
    )
    (net (code "122") (name "Net-(U1-V3)") (class "Default")
      (node (ref "C3") (pin "2") (pinfunction "2_2") (pintype "passive"))
      (node (ref "U1") (pin "4") (pinfunction "V3_4") (pintype "passive"))
    )
    (net (code "123") (name "Net-(U7-1C)") (class "Default")
      (node (ref "J65") (pin "1") (pinfunction "1_1") (pintype "passive"))
      (node (ref "U7") (pin "18") (pinfunction "1C_18") (pintype "passive"))
    )
    (net (code "124") (name "Net-(U7-2C)") (class "Default")
      (node (ref "J66") (pin "1") (pinfunction "1_1") (pintype "passive"))
      (node (ref "U7") (pin "17") (pinfunction "2C_17") (pintype "passive"))
    )
    (net (code "125") (name "Net-(U7-3C)") (class "Default")
      (node (ref "J67") (pin "1") (pinfunction "1_1") (pintype "passive"))
      (node (ref "U7") (pin "16") (pinfunction "3C_16") (pintype "passive"))
    )
    (net (code "126") (name "Net-(U7-4C)") (class "Default")
      (node (ref "J68") (pin "1") (pinfunction "1_1") (pintype "passive"))
      (node (ref "U7") (pin "15") (pinfunction "4C_15") (pintype "passive"))
    )
    (net (code "127") (name "Net-(U7-5C)") (class "Default")
      (node (ref "J69") (pin "1") (pinfunction "1_1") (pintype "passive"))
      (node (ref "U7") (pin "14") (pinfunction "5C_14") (pintype "passive"))
    )
    (net (code "128") (name "Net-(U7-6C)") (class "Default")
      (node (ref "J70") (pin "1") (pinfunction "1_1") (pintype "passive"))
      (node (ref "U7") (pin "13") (pinfunction "6C_13") (pintype "passive"))
    )
    (net (code "129") (name "Net-(U7-7C)") (class "Default")
      (node (ref "J71") (pin "1") (pinfunction "1_1") (pintype "passive"))
      (node (ref "U7") (pin "12") (pinfunction "7C_12") (pintype "passive"))
    )
    (net (code "130") (name "Net-(U7-8C)") (class "Default")
      (node (ref "J72") (pin "1") (pinfunction "1_1") (pintype "passive"))
      (node (ref "U7") (pin "11") (pinfunction "8C_11") (pintype "passive"))
    )
    (net (code "131") (name "Net-(U14-DATA)") (class "Default")
      (node (ref "R1") (pin "1") (pinfunction "1_1") (pintype "passive"))
      (node (ref "R2") (pin "2") (pinfunction "2_2") (pintype "passive"))
      (node (ref "U14") (pin "1") (pinfunction "DATA_1") (pintype "passive"))
    )
    (net (code "132") (name "unconnected-(SW1-Pad1)") (class "Default")
      (node (ref "SW1") (pin "1") (pinfunction "1_1") (pintype "passive"))
    )
    (net (code "133") (name "unconnected-(U1-CTS#-Pad9)") (class "Default")
      (node (ref "U1") (pin "9") (pinfunction "CTS#_9") (pintype "passive"))
    )
    (net (code "134") (name "unconnected-(U1-DCD#-Pad12)") (class "Default")
      (node (ref "U1") (pin "12") (pinfunction "DCD#_12") (pintype "passive"))
    )
    (net (code "135") (name "unconnected-(U1-DSR#-Pad10)") (class "Default")
      (node (ref "U1") (pin "10") (pinfunction "DSR#_10") (pintype "passive"))
    )
    (net (code "136") (name "unconnected-(U1-DTR#-Pad13)") (class "Default")
      (node (ref "U1") (pin "13") (pinfunction "DTR#_13") (pintype "passive"))
    )
    (net (code "137") (name "unconnected-(U1-RI#-Pad11)") (class "Default")
      (node (ref "U1") (pin "11") (pinfunction "RI#_11") (pintype "passive"))
    )
    (net (code "138") (name "unconnected-(U1-RS232-Pad15)") (class "Default")
      (node (ref "U1") (pin "15") (pinfunction "RS232_15") (pintype "passive"))
    )
    (net (code "139") (name "unconnected-(U1-RTS#-Pad14)") (class "Default")
      (node (ref "U1") (pin "14") (pinfunction "RTS#_14") (pintype "passive"))
    )
    (net (code "140") (name "unconnected-(U11-Q7'-Pad9)") (class "Default")
      (node (ref "U11") (pin "9") (pinfunction "Q7'_9") (pintype "passive"))
    )
    (net (code "141") (name "unconnected-(U13-CK_IN-Pad10)") (class "Default")
      (node (ref "U13") (pin "10") (pinfunction "CK_IN_10") (pintype "passive"))
    )
    (net (code "142") (name "unconnected-(U13-CK_OUT-Pad9)") (class "Default")
      (node (ref "U13") (pin "9") (pinfunction "CK_OUT_9") (pintype "passive"))
    )
    (net (code "143") (name "unconnected-(U13-DAT1-Pad8)") (class "Default")
      (node (ref "U13") (pin "8") (pinfunction "DAT1_8") (pintype "passive"))
    )
    (net (code "144") (name "unconnected-(U13-DAT2-Pad1)") (class "Default")
      (node (ref "U13") (pin "1") (pinfunction "DAT2_1") (pintype "passive"))
    )
    (net (code "145") (name "unconnected-(USB1-OTG-Pad4)") (class "Default")
      (node (ref "USB1") (pin "4") (pinfunction "OTG_4") (pintype "passive"))
    )
  )
)
